# REF-IN-BLE-NS_4-0.net
KiCad netlist of a schematic drawn in EAGLE
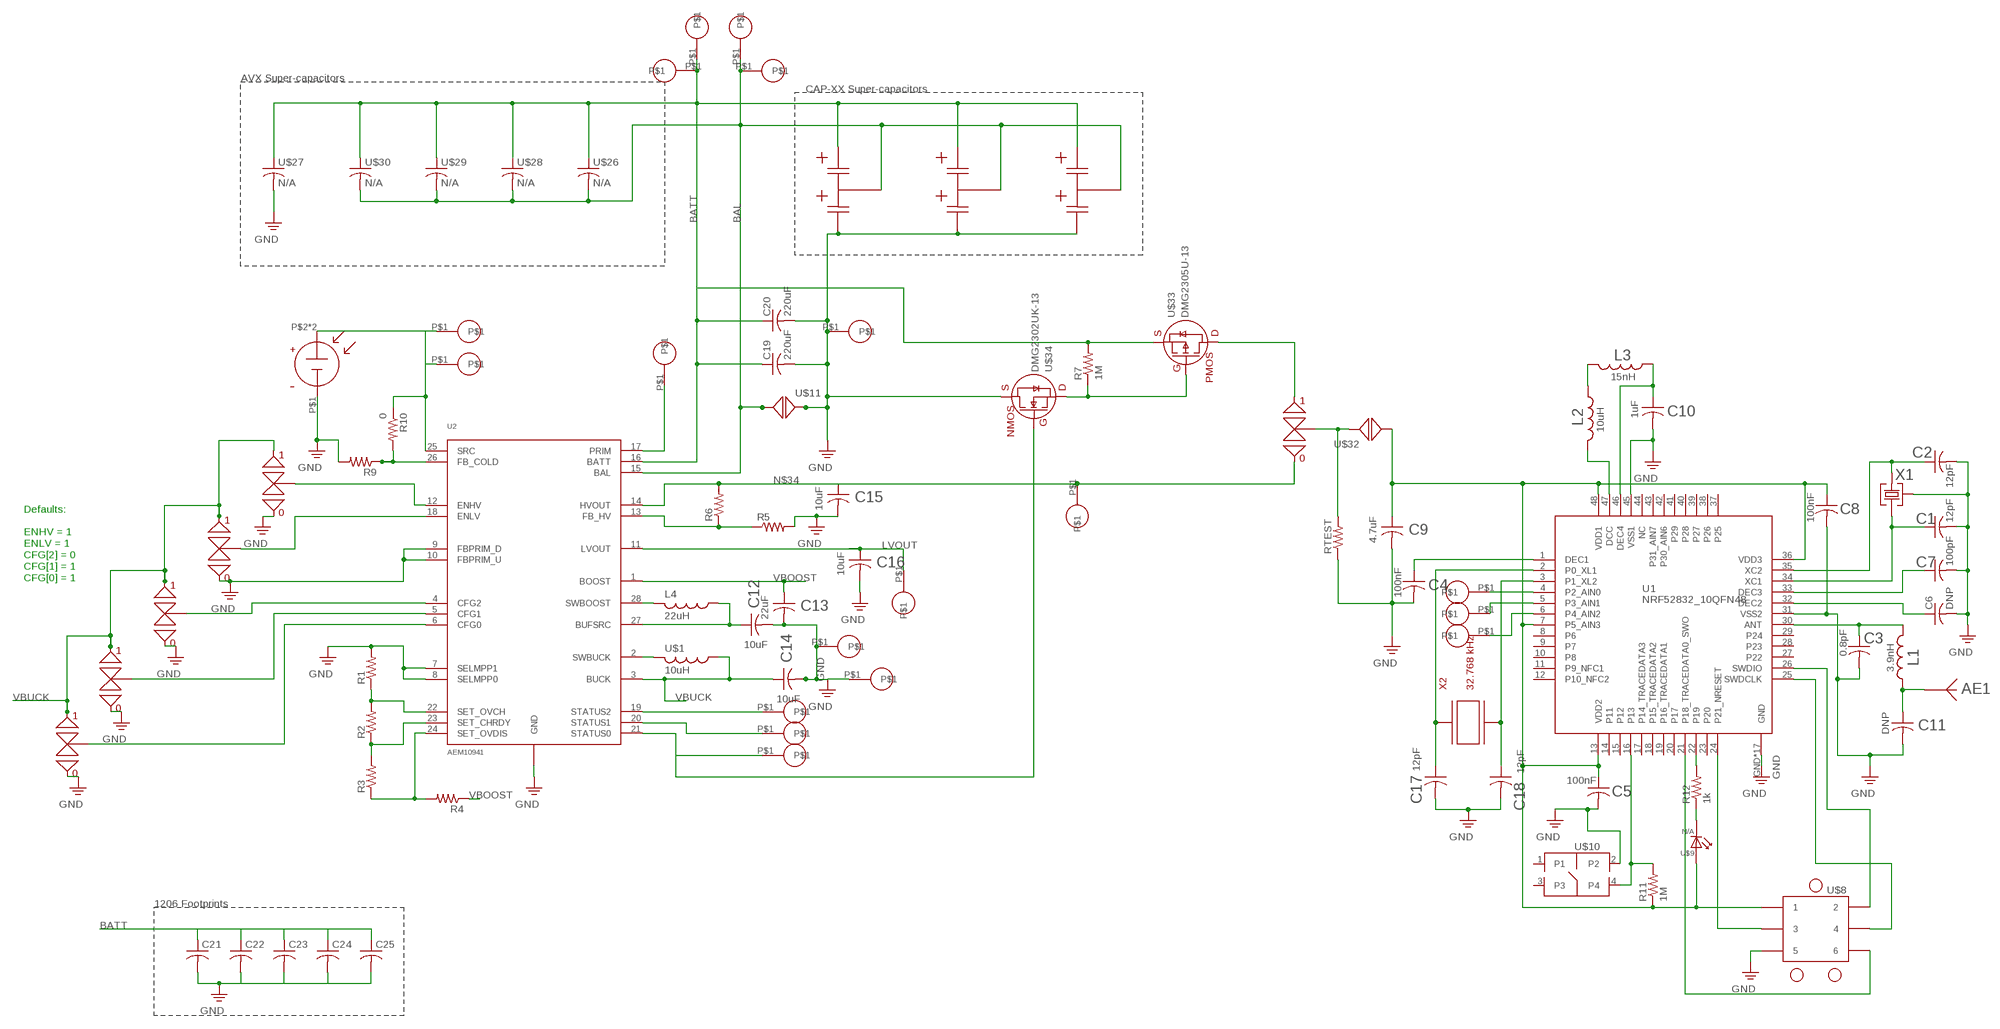
[diagram p0: schematic, sheet 1]

(export (version "E")
  (design (tool "Eeschema 10.0.6"))
  (components
    (comp (ref "AE1")
      (value "N/A")
      (footprint "eagle-import:BLE_ANTENNA_NORDIC")
      (libsource (lib "eagle-import") (part "2.4GHZ_ANTENNA"))
    )
    (comp (ref "C1")
      (value "12pF")
      (footprint "eagle-import:C0603")
      (fields (field (name "MFG_PART#") "C0603C120J5GACTU"))
      (libsource (lib "eagle-import") (part "C-USC0603T-12PF"))
    )
    (comp (ref "C2")
      (value "12pF")
      (footprint "eagle-import:C0603")
      (fields (field (name "MFG_PART#") "C0603C120J5GACTU"))
      (libsource (lib "eagle-import") (part "C-USC0603T-12PF"))
    )
    (comp (ref "C3")
      (value "0.8pF")
      (footprint "eagle-import:C0603")
      (fields (field (name "MFG_PART#") "CBR06C808B5GAC "))
      (libsource (lib "eagle-import") (part "C-USC0603T-0.8PF"))
    )
    (comp (ref "C4")
      (value "100nF")
      (footprint "eagle-import:C0603")
      (fields (field (name "MFG_PART#") "CL10B104KB8NNNC"))
      (libsource (lib "eagle-import") (part "C-USC0603T-100NF"))
    )
    (comp (ref "C5")
      (value "100nF")
      (footprint "eagle-import:C0603")
      (fields (field (name "MFG_PART#") "CL10B104KB8NNNC"))
      (libsource (lib "eagle-import") (part "C-USC0603T-100NF"))
    )
    (comp (ref "C6")
      (value "DNP")
      (footprint "eagle-import:C0603")
      (libsource (lib "eagle-import") (part "C-USC0603"))
    )
    (comp (ref "C7")
      (value "100pF")
      (footprint "eagle-import:C0603")
      (fields (field (name "MFG_PART#") "CL10C101JB8NNNC"))
      (libsource (lib "eagle-import") (part "C-USC0603T-100PF"))
    )
    (comp (ref "C8")
      (value "100nF")
      (footprint "eagle-import:C0603")
      (fields (field (name "MFG_PART#") "CL10B104KB8NNNC"))
      (libsource (lib "eagle-import") (part "C-USC0603T-100NF"))
    )
    (comp (ref "C9")
      (value "4.7uF")
      (footprint "eagle-import:C0603")
      (fields (field (name "MFG_PART#") "CL10A475KQ8NNWC "))
      (libsource (lib "eagle-import") (part "C-USC0603T-4.7UF"))
    )
    (comp (ref "C10")
      (value "1uF")
      (footprint "eagle-import:C0603")
      (fields (field (name "MFG_PART#") "CL10A105KP8NNNC ") (field (name "PERCENTAGE") "10%"))
      (libsource (lib "eagle-import") (part "C-USC0603T-1UF"))
    )
    (comp (ref "C11")
      (value "DNP")
      (footprint "eagle-import:C0603")
      (libsource (lib "eagle-import") (part "C-USC0603"))
    )
    (comp (ref "C12")
      (value "10uF")
      (footprint "eagle-import:C0603")
      (fields (field (name "MFG_PART#") "GRM188R61E106MA73D"))
      (libsource (lib "eagle-import") (part "C-USC0603T-10UF"))
    )
    (comp (ref "C13")
      (value "22uF")
      (footprint "eagle-import:C0603")
      (fields (field (name "MFG_PART#") "GRM188R61A226ME15D"))
      (libsource (lib "eagle-import") (part "C-USC0603T-22UF"))
    )
    (comp (ref "C14")
      (value "10uF")
      (footprint "eagle-import:C0603")
      (fields (field (name "MFG_PART#") "GRM188R61E106MA73D"))
      (libsource (lib "eagle-import") (part "C-USC0603T-10UF"))
    )
    (comp (ref "C15")
      (value "10uF")
      (footprint "eagle-import:C0603")
      (fields (field (name "MFG_PART#") "GRM188R61E106MA73D"))
      (libsource (lib "eagle-import") (part "C-USC0603T-10UF"))
    )
    (comp (ref "C16")
      (value "10uF")
      (footprint "eagle-import:C0603")
      (fields (field (name "MFG_PART#") "GRM188R61E106MA73D"))
      (libsource (lib "eagle-import") (part "C-USC0603T-10UF"))
    )
    (comp (ref "C17")
      (value "12pF")
      (footprint "eagle-import:C0603")
      (fields (field (name "MFG_PART#") "C0603C120J5GACTU"))
      (libsource (lib "eagle-import") (part "C-USC0603T-12PF"))
    )
    (comp (ref "C18")
      (value "12pF")
      (footprint "eagle-import:C0603")
      (fields (field (name "MFG_PART#") "C0603C120J5GACTU"))
      (libsource (lib "eagle-import") (part "C-USC0603T-12PF"))
    )
    (comp (ref "C19")
      (value "220uF")
      (footprint "eagle-import:C1206")
      (fields (field (name "MFG_PART#") "GRM31CC80G227ME11L"))
      (libsource (lib "eagle-import") (part "C-USC1206T-220UF"))
    )
    (comp (ref "C20")
      (value "220uF")
      (footprint "eagle-import:C1206")
      (fields (field (name "MFG_PART#") "GRM31CC80G227ME11L"))
      (libsource (lib "eagle-import") (part "C-USC1206T-220UF"))
    )
    (comp (ref "C21")
      (value "C-USC1206")
      (footprint "eagle-import:C1206")
      (libsource (lib "eagle-import") (part "C-USC1206"))
    )
    (comp (ref "C22")
      (value "C-USC1206")
      (footprint "eagle-import:C1206")
      (libsource (lib "eagle-import") (part "C-USC1206"))
    )
    (comp (ref "C23")
      (value "C-USC1206")
      (footprint "eagle-import:C1206")
      (libsource (lib "eagle-import") (part "C-USC1206"))
    )
    (comp (ref "C24")
      (value "C-USC1206")
      (footprint "eagle-import:C1206")
      (libsource (lib "eagle-import") (part "C-USC1206"))
    )
    (comp (ref "C25")
      (value "C-USC1206")
      (footprint "eagle-import:C1206")
      (libsource (lib "eagle-import") (part "C-USC1206"))
    )
    (comp (ref "L1")
      (value "3.9nH")
      (footprint "eagle-import:L0603")
      (fields (field (name "MFG_PART#") "L-14C3N9SV4T "))
      (libsource (lib "eagle-import") (part "L0603V-3.9NH"))
    )
    (comp (ref "L2")
      (value "10uH")
      (footprint "eagle-import:L0603")
      (fields (field (name "MFG_PART#") "LBR2012T100M"))
      (libsource (lib "eagle-import") (part "L0603V-10UH"))
    )
    (comp (ref "L3")
      (value "15nH")
      (footprint "eagle-import:L0603")
      (fields (field (name "MFG_PART#") "L-14C15NJV4T"))
      (libsource (lib "eagle-import") (part "L0603V-15NH"))
    )
    (comp (ref "L4")
      (value "22uH")
      (footprint "eagle-import:744031220")
      (fields (field (name "MFG_PART#") "744031220"))
      (libsource (lib "eagle-import") (part "744031220"))
    )
    (comp (ref "R1")
      (value "R-US_R0603")
      (footprint "eagle-import:R0603")
      (libsource (lib "eagle-import") (part "R-US_R0603"))
    )
    (comp (ref "R2")
      (value "R-US_R0603")
      (footprint "eagle-import:R0603")
      (libsource (lib "eagle-import") (part "R-US_R0603"))
    )
    (comp (ref "R3")
      (value "R-US_R0603")
      (footprint "eagle-import:R0603")
      (libsource (lib "eagle-import") (part "R-US_R0603"))
    )
    (comp (ref "R4")
      (value "R-US_R0603")
      (footprint "eagle-import:R0603")
      (libsource (lib "eagle-import") (part "R-US_R0603"))
    )
    (comp (ref "R5")
      (value "R-US_R0603")
      (footprint "eagle-import:R0603")
      (libsource (lib "eagle-import") (part "R-US_R0603"))
    )
    (comp (ref "R6")
      (value "R-US_R0603")
      (footprint "eagle-import:R0603")
      (libsource (lib "eagle-import") (part "R-US_R0603"))
    )
    (comp (ref "R7")
      (value "1M")
      (footprint "eagle-import:R0603")
      (libsource (lib "eagle-import") (part "R-US_R0603"))
    )
    (comp (ref "R9")
      (value "R-US_R0603")
      (footprint "eagle-import:R0603")
      (libsource (lib "eagle-import") (part "R-US_R0603"))
    )
    (comp (ref "R10")
      (value "0")
      (footprint "eagle-import:R0603")
      (libsource (lib "eagle-import") (part "R-US_R0603"))
    )
    (comp (ref "R11")
      (value "1M")
      (footprint "eagle-import:R0603")
      (libsource (lib "eagle-import") (part "R-US_R0603"))
    )
    (comp (ref "R12")
      (value "1k")
      (footprint "eagle-import:R0603")
      (libsource (lib "eagle-import") (part "R-US_R0603"))
    )
    (comp (ref "RTEST")
      (value "R-US_R0603")
      (footprint "eagle-import:R0603")
      (libsource (lib "eagle-import") (part "R-US_R0603"))
    )
    (comp (ref "U$1")
      (value "10uH")
      (footprint "eagle-import:L0603")
      (fields (field (name "MFG_PART#") "LBR2012T100M"))
      (libsource (lib "eagle-import") (part "L0603V-10UH"))
    )
    (comp (ref "U$2")
      (value "DOUBLE_SOLDER_BRIDGE1_CLOSED")
      (footprint "eagle-import:DOUBLE_SOLDER_BRIDGE_1_CLOSED")
      (libsource (lib "eagle-import") (part "DOUBLE_SOLDER_BRIDGE1_CLOSED"))
    )
    (comp (ref "U$3")
      (value "DOUBLE_SOLDER_BRIDGE1_CLOSED")
      (footprint "eagle-import:DOUBLE_SOLDER_BRIDGE_1_CLOSED")
      (libsource (lib "eagle-import") (part "DOUBLE_SOLDER_BRIDGE1_CLOSED"))
    )
    (comp (ref "U$4")
      (value "N/A")
      (footprint "eagle-import:DOUBLE_SOLDER_BRIDGE_0_CLOSED")
      (libsource (lib "eagle-import") (part "DOUBLE_SOLDER_BRIDGE0_CLOSED"))
    )
    (comp (ref "U$5")
      (value "DOUBLE_SOLDER_BRIDGE1_CLOSED")
      (footprint "eagle-import:DOUBLE_SOLDER_BRIDGE_1_CLOSED")
      (libsource (lib "eagle-import") (part "DOUBLE_SOLDER_BRIDGE1_CLOSED"))
    )
    (comp (ref "U$6")
      (value "DOUBLE_SOLDER_BRIDGE1_CLOSED")
      (footprint "eagle-import:DOUBLE_SOLDER_BRIDGE_1_CLOSED")
      (libsource (lib "eagle-import") (part "DOUBLE_SOLDER_BRIDGE1_CLOSED"))
    )
    (comp (ref "U$7")
      (value "N/A")
      (footprint "eagle-import:SOLAR_CELL_37X54MM")
      (libsource (lib "eagle-import") (part "SOLAR_CELL"))
    )
    (comp (ref "U$8")
      (value "N/A")
      (footprint "eagle-import:TC2030-IDC")
      (libsource (lib "eagle-import") (part "TC2030-IDC"))
    )
    (comp (ref "U$9")
      (value "N/A")
      (footprint "eagle-import:APT1608LZGCK")
      (fields (field (name "MFG_PART#") "APT1608LZGCK"))
      (libsource (lib "eagle-import") (part "APT1608LZGCK"))
    )
    (comp (ref "U$10")
      (value "MJTP1140")
      (footprint "eagle-import:MJTP1140A")
      (fields (field (name "MFG_PART#") "TL3315NF100Q "))
      (libsource (lib "eagle-import") (part "MJTP1140"))
    )
    (comp (ref "U$11")
      (value "SOLDER_BRIGDECLOSED")
      (footprint "eagle-import:SOLDER_BRIDGE_CLOSED")
      (libsource (lib "eagle-import") (part "SOLDER_BRIGDECLOSED"))
    )
    (comp (ref "U$12")
      (value "N/A")
      (footprint "eagle-import:1MM_PAD")
      (libsource (lib "eagle-import") (part "1MM_PAD"))
    )
    (comp (ref "U$13")
      (value "N/A")
      (footprint "eagle-import:1MM_PAD")
      (libsource (lib "eagle-import") (part "1MM_PAD"))
    )
    (comp (ref "U$14")
      (value "N/A")
      (footprint "eagle-import:1MM_PAD")
      (libsource (lib "eagle-import") (part "1MM_PAD"))
    )
    (comp (ref "U$15")
      (value "N/A")
      (footprint "eagle-import:1MM_PAD")
      (libsource (lib "eagle-import") (part "1MM_PAD"))
    )
    (comp (ref "U$16")
      (value "N/A")
      (footprint "eagle-import:1MM_PAD")
      (libsource (lib "eagle-import") (part "1MM_PAD"))
    )
    (comp (ref "U$17")
      (value "N/A")
      (footprint "eagle-import:1MM_PAD")
      (libsource (lib "eagle-import") (part "1MM_PAD"))
    )
    (comp (ref "U$18")
      (value "N/A")
      (footprint "eagle-import:1MM_PAD")
      (libsource (lib "eagle-import") (part "1MM_PAD"))
    )
    (comp (ref "U$19")
      (value "N/A")
      (footprint "eagle-import:1MM_PAD")
      (libsource (lib "eagle-import") (part "1MM_PAD"))
    )
    (comp (ref "U$20")
      (value "N/A")
      (footprint "eagle-import:1MM_PAD")
      (libsource (lib "eagle-import") (part "1MM_PAD"))
    )
    (comp (ref "U$21")
      (value "N/A")
      (footprint "eagle-import:1MM_PAD")
      (libsource (lib "eagle-import") (part "1MM_PAD"))
    )
    (comp (ref "U$22")
      (value "N/A")
      (footprint "eagle-import:1MM_PAD")
      (libsource (lib "eagle-import") (part "1MM_PAD"))
    )
    (comp (ref "U$23")
      (value "N/A")
      (footprint "eagle-import:CAP-XX_A-TYPE")
      (libsource (lib "eagle-import") (part "CAP-XX_A-TYPE"))
    )
    (comp (ref "U$24")
      (value "N/A")
      (footprint "eagle-import:CAP-XX_S-TYPE")
      (libsource (lib "eagle-import") (part "CAP-XX_S-TYPE"))
    )
    (comp (ref "U$25")
      (value "N/A")
      (footprint "eagle-import:CAP-XX_W-TYPE")
      (libsource (lib "eagle-import") (part "CAP-XX_W-TYPE"))
    )
    (comp (ref "U$26")
      (value "N/A")
      (footprint "eagle-import:BZ01_L-TYPE")
      (libsource (lib "eagle-import") (part "BZ01_L-TYPE"))
    )
    (comp (ref "U$27")
      (value "N/A")
      (footprint "eagle-import:BZ059_N-TYPE")
      (libsource (lib "eagle-import") (part "BZ059_N-TYPE"))
    )
    (comp (ref "U$28")
      (value "N/A")
      (footprint "eagle-import:BZ01_S-TYPE")
      (libsource (lib "eagle-import") (part "BZ01_S-TYPE"))
    )
    (comp (ref "U$29")
      (value "N/A")
      (footprint "eagle-import:BZ05_S-TYPE")
      (libsource (lib "eagle-import") (part "BZ05_S-TYPE"))
    )
    (comp (ref "U$30")
      (value "N/A")
      (footprint "eagle-import:BZ09_S-TYPE")
      (libsource (lib "eagle-import") (part "BZ09_S-TYPE"))
    )
    (comp (ref "U$31")
      (value "DOUBLE_SOLDER_BRIDGE1_CLOSED")
      (footprint "eagle-import:DOUBLE_SOLDER_BRIDGE_1_CLOSED")
      (libsource (lib "eagle-import") (part "DOUBLE_SOLDER_BRIDGE1_CLOSED"))
    )
    (comp (ref "U$32")
      (value "SOLDER_BRIGDECLOSED")
      (footprint "eagle-import:SOLDER_BRIDGE_CLOSED")
      (libsource (lib "eagle-import") (part "SOLDER_BRIGDECLOSED"))
    )
    (comp (ref "U$33")
      (value "DMG2305U-13")
      (footprint "eagle-import:SOT-23-3-DIODESINC")
      (libsource (lib "eagle-import") (part "DMG2305U-13"))
    )
    (comp (ref "U$34")
      (value "DMG2302UK-13")
      (footprint "eagle-import:SOT-23-3-DIODESINC")
      (libsource (lib "eagle-import") (part "DMG2302UK-13"))
    )
    (comp (ref "U$35")
      (value "N/A")
      (footprint "eagle-import:1MM_PAD")
      (libsource (lib "eagle-import") (part "1MM_PAD"))
    )
    (comp (ref "U$36")
      (value "N/A")
      (footprint "eagle-import:1MM_PAD")
      (libsource (lib "eagle-import") (part "1MM_PAD"))
    )
    (comp (ref "U$37")
      (value "N/A")
      (footprint "eagle-import:1MM_PAD")
      (libsource (lib "eagle-import") (part "1MM_PAD"))
    )
    (comp (ref "U$38")
      (value "N/A")
      (footprint "eagle-import:1MM_PAD")
      (libsource (lib "eagle-import") (part "1MM_PAD"))
    )
    (comp (ref "U$39")
      (value "N/A")
      (footprint "eagle-import:1MM_PAD")
      (libsource (lib "eagle-import") (part "1MM_PAD"))
    )
    (comp (ref "U$40")
      (value "N/A")
      (footprint "eagle-import:1MM_PAD")
      (libsource (lib "eagle-import") (part "1MM_PAD"))
    )
    (comp (ref "U$41")
      (value "N/A")
      (footprint "eagle-import:1MM_PAD")
      (libsource (lib "eagle-import") (part "1MM_PAD"))
    )
    (comp (ref "U1")
      (value "NRF52832_10QFN48")
      (footprint "eagle-import:NRF52832_10")
      (fields (field (name "MFG_PART#") "NRF52832-QFAA-R"))
      (libsource (lib "eagle-import") (part "NRF52832_10QFN48"))
    )
    (comp (ref "U2")
      (value "AEM10941")
      (footprint "eagle-import:QFN28_5X5_05PITCH")
      (fields (field (name "MFG_PART#") "AEM10941-QFN "))
      (libsource (lib "eagle-import") (part "AEM10941"))
    )
    (comp (ref "X1")
      (value "32 MHz")
      (footprint "eagle-import:FA-128-EPSON")
      (fields (field (name "MFG_PART#") "FA-128 32.0000MF10Z-AJ3"))
      (libsource (lib "eagle-import") (part "FA-128-32MHZMF10Z-AJ5"))
    )
    (comp (ref "X2")
      (value "32.768 kHz")
      (footprint "eagle-import:FC-135")
      (fields (field (name "MFG_PART#") "FC-135 32.7680KA-AC"))
      (libsource (lib "eagle-import") (part "FC-135_32.7680KA-AC"))
    )
  )
  (nets
    (net (code "1") (name "/BAL") (class "Default")
      (node (ref "U$11") (pin "P$1") (pinfunction "P1_P$1") (pintype "bidirectional"))
      (node (ref "U$19") (pin "P$1") (pinfunction "P$1_P$1") (pintype "bidirectional"))
      (node (ref "U$23") (pin "P$1") (pinfunction "BAL_P$1") (pintype "bidirectional"))
      (node (ref "U$24") (pin "P$1") (pinfunction "BAL_P$1") (pintype "bidirectional"))
      (node (ref "U$25") (pin "P$1") (pinfunction "BAL_P$1") (pintype "bidirectional"))
      (node (ref "U$26") (pin "P$3") (pinfunction "2_P$3") (pintype "passive"))
      (node (ref "U$26") (pin "P$4") (pinfunction "2_P$4") (pintype "passive"))
      (node (ref "U$28") (pin "P$3") (pinfunction "2_P$3") (pintype "passive"))
      (node (ref "U$29") (pin "P$3") (pinfunction "2_P$3") (pintype "passive"))
      (node (ref "U$30") (pin "P$3") (pinfunction "2_P$3") (pintype "passive"))
      (node (ref "U$41") (pin "P$1") (pinfunction "P$1_P$1") (pintype "bidirectional"))
      (node (ref "U2") (pin "15") (pinfunction "BAL_15") (pintype "bidirectional"))
    )
    (net (code "2") (name "/BATT") (class "Default")
      (node (ref "C19") (pin "1") (pinfunction "1_1") (pintype "passive"))
      (node (ref "C20") (pin "1") (pinfunction "1_1") (pintype "passive"))
      (node (ref "C21") (pin "1") (pinfunction "1_1") (pintype "passive"))
      (node (ref "C22") (pin "1") (pinfunction "1_1") (pintype "passive"))
      (node (ref "C23") (pin "1") (pinfunction "1_1") (pintype "passive"))
      (node (ref "C24") (pin "1") (pinfunction "1_1") (pintype "passive"))
      (node (ref "C25") (pin "1") (pinfunction "1_1") (pintype "passive"))
      (node (ref "R7") (pin "2") (pinfunction "2_2") (pintype "passive"))
      (node (ref "U$18") (pin "P$1") (pinfunction "P$1_P$1") (pintype "bidirectional"))
      (node (ref "U$23") (pin "P$2") (pinfunction "+_P$2") (pintype "bidirectional"))
      (node (ref "U$24") (pin "P$2") (pinfunction "+_P$2") (pintype "bidirectional"))
      (node (ref "U$25") (pin "P$2") (pinfunction "+_P$2") (pintype "bidirectional"))
      (node (ref "U$26") (pin "P$1") (pinfunction "1_P$1") (pintype "passive"))
      (node (ref "U$26") (pin "P$2") (pinfunction "1_P$2") (pintype "passive"))
      (node (ref "U$27") (pin "P$1") (pinfunction "1_P$1") (pintype "passive"))
      (node (ref "U$28") (pin "P$1") (pinfunction "1_P$1") (pintype "passive"))
      (node (ref "U$28") (pin "P$2") (pinfunction "1_P$2") (pintype "passive"))
      (node (ref "U$29") (pin "P$1") (pinfunction "1_P$1") (pintype "passive"))
      (node (ref "U$29") (pin "P$2") (pinfunction "1_P$2") (pintype "passive"))
      (node (ref "U$30") (pin "P$1") (pinfunction "1_P$1") (pintype "passive"))
      (node (ref "U$30") (pin "P$2") (pinfunction "1_P$2") (pintype "passive"))
      (node (ref "U$33") (pin "2") (pinfunction "S_2") (pintype "bidirectional"))
      (node (ref "U$40") (pin "P$1") (pinfunction "P$1_P$1") (pintype "bidirectional"))
      (node (ref "U2") (pin "16") (pinfunction "BATT_16") (pintype "bidirectional"))
    )
    (net (code "3") (name "/LVOUT") (class "Default")
      (node (ref "C16") (pin "1") (pinfunction "1_1") (pintype "passive"))
      (node (ref "U$16") (pin "P$1") (pinfunction "P$1_P$1") (pintype "bidirectional"))
      (node (ref "U2") (pin "11") (pinfunction "LVOUT_11") (pintype "output"))
    )
    (net (code "4") (name "/N$34") (class "Default")
      (node (ref "C15") (pin "1") (pinfunction "1_1") (pintype "passive"))
      (node (ref "R6") (pin "2") (pinfunction "2_2") (pintype "passive"))
      (node (ref "U$31") (pin "IN0") (pinfunction "IN0_IN0") (pintype "bidirectional"))
      (node (ref "U$37") (pin "P$1") (pinfunction "P$1_P$1") (pintype "bidirectional"))
      (node (ref "U2") (pin "14") (pinfunction "HVOUT_14") (pintype "output"))
    )
    (net (code "5") (name "/VBOOST") (class "Default")
      (node (ref "C13") (pin "1") (pinfunction "1_1") (pintype "passive"))
      (node (ref "R4") (pin "1") (pinfunction "1_1") (pintype "passive"))
      (node (ref "U2") (pin "1") (pinfunction "BOOST_1") (pintype "bidirectional"))
    )
    (net (code "6") (name "/VBUCK") (class "Default")
      (node (ref "C14") (pin "1") (pinfunction "1_1") (pintype "passive"))
      (node (ref "U$1") (pin "1") (pinfunction "1_1") (pintype "passive"))
      (node (ref "U$2") (pin "IN1") (pinfunction "IN1_IN1") (pintype "bidirectional"))
      (node (ref "U$3") (pin "IN1") (pinfunction "IN1_IN1") (pintype "bidirectional"))
      (node (ref "U$4") (pin "IN1") (pinfunction "IN1_IN1") (pintype "bidirectional"))
      (node (ref "U$5") (pin "IN1") (pinfunction "IN1_IN1") (pintype "bidirectional"))
      (node (ref "U$6") (pin "IN1") (pinfunction "IN1_IN1") (pintype "bidirectional"))
      (node (ref "U2") (pin "3") (pinfunction "BUCK_3") (pintype "bidirectional"))
    )
    (net (code "7") (name "GND") (class "Default")
      (node (ref "C1") (pin "2") (pinfunction "2_2") (pintype "passive"))
      (node (ref "C10") (pin "2") (pinfunction "2_2") (pintype "passive"))
      (node (ref "C11") (pin "2") (pinfunction "2_2") (pintype "passive"))
      (node (ref "C12") (pin "2") (pinfunction "2_2") (pintype "passive"))
      (node (ref "C13") (pin "2") (pinfunction "2_2") (pintype "passive"))
      (node (ref "C14") (pin "2") (pinfunction "2_2") (pintype "passive"))
      (node (ref "C15") (pin "2") (pinfunction "2_2") (pintype "passive"))
      (node (ref "C16") (pin "2") (pinfunction "2_2") (pintype "passive"))
      (node (ref "C17") (pin "2") (pinfunction "2_2") (pintype "passive"))
      (node (ref "C18") (pin "2") (pinfunction "2_2") (pintype "passive"))
      (node (ref "C19") (pin "2") (pinfunction "2_2") (pintype "passive"))
      (node (ref "C2") (pin "2") (pinfunction "2_2") (pintype "passive"))
      (node (ref "C20") (pin "2") (pinfunction "2_2") (pintype "passive"))
      (node (ref "C21") (pin "2") (pinfunction "2_2") (pintype "passive"))
      (node (ref "C22") (pin "2") (pinfunction "2_2") (pintype "passive"))
      (node (ref "C23") (pin "2") (pinfunction "2_2") (pintype "passive"))
      (node (ref "C24") (pin "2") (pinfunction "2_2") (pintype "passive"))
      (node (ref "C25") (pin "2") (pinfunction "2_2") (pintype "passive"))
      (node (ref "C3") (pin "2") (pinfunction "2_2") (pintype "passive"))
      (node (ref "C4") (pin "2") (pinfunction "2_2") (pintype "passive"))
      (node (ref "C5") (pin "2") (pinfunction "2_2") (pintype "passive"))
      (node (ref "C6") (pin "2") (pinfunction "2_2") (pintype "passive"))
      (node (ref "C7") (pin "2") (pinfunction "2_2") (pintype "passive"))
      (node (ref "C8") (pin "2") (pinfunction "2_2") (pintype "passive"))
      (node (ref "C9") (pin "2") (pinfunction "2_2") (pintype "passive"))
      (node (ref "R1") (pin "2") (pinfunction "2_2") (pintype "passive"))
      (node (ref "R5") (pin "2") (pinfunction "2_2") (pintype "passive"))
      (node (ref "R9") (pin "2") (pinfunction "2_2") (pintype "passive"))
      (node (ref "RTEST") (pin "1") (pinfunction "1_1") (pintype "passive"))
      (node (ref "U$10") (pin "2") (pinfunction "P2_2") (pintype "bidirectional"))
      (node (ref "U$11") (pin "P$2") (pinfunction "P2_P$2") (pintype "bidirectional"))
      (node (ref "U$17") (pin "P$1") (pinfunction "P$1_P$1") (pintype "bidirectional"))
      (node (ref "U$2") (pin "IN0") (pinfunction "IN0_IN0") (pintype "bidirectional"))
      (node (ref "U$23") (pin "P$3") (pinfunction "-_P$3") (pintype "bidirectional"))
      (node (ref "U$24") (pin "P$3") (pinfunction "-_P$3") (pintype "bidirectional"))
      (node (ref "U$25") (pin "P$3") (pinfunction "-_P$3") (pintype "bidirectional"))
      (node (ref "U$27") (pin "P$2") (pinfunction "2_P$2") (pintype "passive"))
      (node (ref "U$3") (pin "IN0") (pinfunction "IN0_IN0") (pintype "bidirectional"))
      (node (ref "U$34") (pin "3") (pinfunction "S_3") (pintype "bidirectional"))
      (node (ref "U$35") (pin "P$1") (pinfunction "P$1_P$1") (pintype "bidirectional"))
      (node (ref "U$38") (pin "P$1") (pinfunction "P$1_P$1") (pintype "bidirectional"))
      (node (ref "U$4") (pin "IN0") (pinfunction "IN0_IN0") (pintype "bidirectional"))
      (node (ref "U$5") (pin "IN0") (pinfunction "IN0_IN0") (pintype "bidirectional"))
      (node (ref "U$6") (pin "IN0") (pinfunction "IN0_IN0") (pintype "bidirectional"))
      (node (ref "U$7") (pin "P$1") (pinfunction "GND_P$1") (pintype "bidirectional"))
      (node (ref "U$8") (pin "P5") (pinfunction "5_P5") (pintype "bidirectional"))
      (node (ref "U1") (pin "31") (pinfunction "VSS2_31") (pintype "bidirectional"))
      (node (ref "U1") (pin "45") (pinfunction "VSS1_45") (pintype "bidirectional"))
      (node (ref "U1") (pin "GND") (pinfunction "GND_GND") (pintype "bidirectional"))
      (node (ref "U1") (pin "P$10") (pinfunction "GND_P$10") (pintype "bidirectional"))
      (node (ref "U1") (pin "P$11") (pinfunction "GND_P$11") (pintype "bidirectional"))
      (node (ref "U1") (pin "P$12") (pinfunction "GND_P$12") (pintype "bidirectional"))
      (node (ref "U1") (pin "P$13") (pinfunction "GND_P$13") (pintype "bidirectional"))
      (node (ref "U1") (pin "P$14") (pinfunction "GND_P$14") (pintype "bidirectional"))
      (node (ref "U1") (pin "P$15") (pinfunction "GND_P$15") (pintype "bidirectional"))
      (node (ref "U1") (pin "P$16") (pinfunction "GND_P$16") (pintype "bidirectional"))
      (node (ref "U1") (pin "P$17") (pinfunction "GND_P$17") (pintype "bidirectional"))
      (node (ref "U1") (pin "P$2") (pinfunction "GND_P$2") (pintype "bidirectional"))
      (node (ref "U1") (pin "P$3") (pinfunction "GND_P$3") (pintype "bidirectional"))
      (node (ref "U1") (pin "P$4") (pinfunction "GND_P$4") (pintype "bidirectional"))
      (node (ref "U1") (pin "P$5") (pinfunction "GND_P$5") (pintype "bidirectional"))
      (node (ref "U1") (pin "P$6") (pinfunction "GND_P$6") (pintype "bidirectional"))
      (node (ref "U1") (pin "P$7") (pinfunction "GND_P$7") (pintype "bidirectional"))
      (node (ref "U1") (pin "P$8") (pinfunction "GND_P$8") (pintype "bidirectional"))
      (node (ref "U1") (pin "P$9") (pinfunction "GND_P$9") (pintype "bidirectional"))
      (node (ref "U2") (pin "10") (pinfunction "FBPRIM_U_10") (pintype "bidirectional"))
      (node (ref "U2") (pin "7") (pinfunction "SELMPP1_7") (pintype "input"))
      (node (ref "U2") (pin "8") (pinfunction "SELMPP0_8") (pintype "input"))
      (node (ref "U2") (pin "9") (pinfunction "FBPRIM_D_9") (pintype "bidirectional"))
      (node (ref "U2") (pin "GND") (pinfunction "GND_GND") (pintype "power_in"))
      (node (ref "U2") (pin "GND1") (pinfunction "GND_GND1") (pintype "power_in"))
      (node (ref "U2") (pin "GND2") (pinfunction "GND_GND2") (pintype "power_in"))
      (node (ref "U2") (pin "GND3") (pinfunction "GND_GND3") (pintype "power_in"))
      (node (ref "U2") (pin "GND4") (pinfunction "GND_GND4") (pintype "power_in"))
      (node (ref "U2") (pin "GND5") (pinfunction "GND_GND5") (pintype "power_in"))
      (node (ref "X1") (pin "P2") (pinfunction "P3_P2") (pintype "bidirectional"))
      (node (ref "X1") (pin "P4") (pinfunction "P3_P4") (pintype "bidirectional"))
    )
    (net (code "8") (name "Net-(AE1-PadP$1)") (class "Default")
      (node (ref "AE1") (pin "P$1") (pinfunction "P$1_P$1") (pintype "bidirectional"))
      (node (ref "C11") (pin "1") (pinfunction "1_1") (pintype "passive"))
      (node (ref "L1") (pin "1") (pinfunction "1_1") (pintype "passive"))
    )
    (net (code "9") (name "Net-(L2-Pad1)") (class "Default")
      (node (ref "L2") (pin "1") (pinfunction "1_1") (pintype "passive"))
      (node (ref "L3") (pin "2") (pinfunction "2_2") (pintype "passive"))
    )
    (net (code "10") (name "Net-(L4-1)") (class "Default")
      (node (ref "C12") (pin "1") (pinfunction "1_1") (pintype "passive"))
      (node (ref "L4") (pin "PIN1") (pinfunction "1_PIN1") (pintype "passive"))
      (node (ref "U2") (pin "27") (pinfunction "BUFSRC_27") (pintype "bidirectional"))
    )
    (net (code "11") (name "Net-(L4-2)") (class "Default")
      (node (ref "L4") (pin "PIN2") (pinfunction "2_PIN2") (pintype "passive"))
      (node (ref "U2") (pin "28") (pinfunction "SWBOOST_28") (pintype "bidirectional"))
    )
    (net (code "12") (name "Net-(R12-Pad1)") (class "Default")
      (node (ref "R12") (pin "1") (pinfunction "1_1") (pintype "passive"))
      (node (ref "U$9") (pin "C") (pinfunction "C_C") (pintype "bidirectional"))
    )
    (net (code "13") (name "Net-(U$8-2)") (class "Default")
      (node (ref "U$8") (pin "P2") (pinfunction "2_P2") (pintype "bidirectional"))
      (node (ref "U1") (pin "26") (pinfunction "SWDIO_26") (pintype "bidirectional"))
    )
    (net (code "14") (name "Net-(U$8-3)") (class "Default")
      (node (ref "U$8") (pin "P3") (pinfunction "3_P3") (pintype "bidirectional"))
      (node (ref "U1") (pin "24") (pinfunction "P21_NRESET_24") (pintype "bidirectional"))
    )
    (net (code "15") (name "Net-(U$8-4)") (class "Default")
      (node (ref "U$8") (pin "P4") (pinfunction "4_P4") (pintype "bidirectional"))
      (node (ref "U1") (pin "25") (pinfunction "SWDCLK_25") (pintype "bidirectional"))
    )
    (net (code "16") (name "Net-(U$8-6)") (class "Default")
      (node (ref "U$8") (pin "P6") (pinfunction "6_P6") (pintype "bidirectional"))
      (node (ref "U1") (pin "21") (pinfunction "P18_TRACEDATA0_SWO_21") (pintype "bidirectional"))
    )
    (net (code "17") (name "Net-(U$10-P4)") (class "Default")
      (node (ref "R11") (pin "2") (pinfunction "2_2") (pintype "passive"))
      (node (ref "U$10") (pin "4") (pinfunction "P4_4") (pintype "bidirectional"))
      (node (ref "U1") (pin "16") (pinfunction "P13_16") (pintype "bidirectional"))
    )
    (net (code "18") (name "Net-(U$32-P1)") (class "Default")
      (node (ref "C5") (pin "1") (pinfunction "1_1") (pintype "passive"))
      (node (ref "C8") (pin "1") (pinfunction "1_1") (pintype "passive"))
      (node (ref "C9") (pin "1") (pinfunction "1_1") (pintype "passive"))
      (node (ref "R11") (pin "1") (pinfunction "1_1") (pintype "passive"))
      (node (ref "U$32") (pin "P$1") (pinfunction "P1_P$1") (pintype "bidirectional"))
      (node (ref "U$8") (pin "P1") (pinfunction "1_P1") (pintype "bidirectional"))
      (node (ref "U$9") (pin "A") (pinfunction "A_A") (pintype "bidirectional"))
      (node (ref "U1") (pin "13") (pinfunction "VDD2_13") (pintype "bidirectional"))
      (node (ref "U1") (pin "36") (pinfunction "VDD3_36") (pintype "bidirectional"))
      (node (ref "U1") (pin "48") (pinfunction "VDD1_48") (pintype "bidirectional"))
      (node (ref "U1") (pin "7") (pinfunction "P5_AIN3_7") (pintype "bidirectional"))
    )
    (net (code "19") (name "Net-(U$32-P2)") (class "Default")
      (node (ref "RTEST") (pin "2") (pinfunction "2_2") (pintype "passive"))
      (node (ref "U$31") (pin "OUT") (pinfunction "OUT_OUT") (pintype "bidirectional"))
      (node (ref "U$32") (pin "P$2") (pinfunction "P2_P$2") (pintype "bidirectional"))
    )
    (net (code "20") (name "Net-(U$33-D)") (class "Default")
      (node (ref "U$31") (pin "IN1") (pinfunction "IN1_IN1") (pintype "bidirectional"))
      (node (ref "U$33") (pin "3") (pinfunction "D_3") (pintype "bidirectional"))
    )
    (net (code "21") (name "Net-(U$33-G)") (class "Default")
      (node (ref "R7") (pin "1") (pinfunction "1_1") (pintype "passive"))
      (node (ref "U$33") (pin "1") (pinfunction "G_1") (pintype "bidirectional"))
      (node (ref "U$34") (pin "2") (pinfunction "D_2") (pintype "bidirectional"))
    )
    (net (code "22") (name "Net-(U$34-G)") (class "Default")
      (node (ref "U$15") (pin "P$1") (pinfunction "P$1_P$1") (pintype "bidirectional"))
      (node (ref "U$34") (pin "1") (pinfunction "G_1") (pintype "bidirectional"))
      (node (ref "U2") (pin "21") (pinfunction "STATUS0_21") (pintype "output"))
    )
    (net (code "23") (name "Net-(U1-ANT)") (class "Default")
      (node (ref "C3") (pin "1") (pinfunction "1_1") (pintype "passive"))
      (node (ref "L1") (pin "2") (pinfunction "2_2") (pintype "passive"))
      (node (ref "U1") (pin "30") (pinfunction "ANT_30") (pintype "bidirectional"))
    )
    (net (code "24") (name "Net-(U1-DCC)") (class "Default")
      (node (ref "L2") (pin "2") (pinfunction "2_2") (pintype "passive"))
      (node (ref "U1") (pin "47") (pinfunction "DCC_47") (pintype "bidirectional"))
    )
    (net (code "25") (name "Net-(U1-DEC1)") (class "Default")
      (node (ref "C4") (pin "1") (pinfunction "1_1") (pintype "passive"))
      (node (ref "U1") (pin "1") (pinfunction "DEC1_1") (pintype "bidirectional"))
    )
    (net (code "26") (name "Net-(U1-DEC2)") (class "Default")
      (node (ref "C6") (pin "1") (pinfunction "1_1") (pintype "passive"))
      (node (ref "U1") (pin "32") (pinfunction "DEC2_32") (pintype "bidirectional"))
    )
    (net (code "27") (name "Net-(U1-DEC3)") (class "Default")
      (node (ref "C7") (pin "1") (pinfunction "1_1") (pintype "passive"))
      (node (ref "U1") (pin "33") (pinfunction "DEC3_33") (pintype "bidirectional"))
    )
    (net (code "28") (name "Net-(U1-DEC4)") (class "Default")
      (node (ref "C10") (pin "1") (pinfunction "1_1") (pintype "passive"))
      (node (ref "L3") (pin "1") (pinfunction "1_1") (pintype "passive"))
      (node (ref "U1") (pin "46") (pinfunction "DEC4_46") (pintype "bidirectional"))
    )
    (net (code "29") (name "Net-(U1-P0_XL1)") (class "Default")
      (node (ref "C17") (pin "1") (pinfunction "1_1") (pintype "passive"))
      (node (ref "U1") (pin "2") (pinfunction "P0_XL1_2") (pintype "bidirectional"))
      (node (ref "X2") (pin "P$1") (pinfunction "P$1_P$1") (pintype "bidirectional"))
    )
    (net (code "30") (name "Net-(U1-P1_XL2)") (class "Default")
      (node (ref "C18") (pin "1") (pinfunction "1_1") (pintype "passive"))
      (node (ref "U1") (pin "3") (pinfunction "P1_XL2_3") (pintype "bidirectional"))
      (node (ref "X2") (pin "P$2") (pinfunction "P$2_P$2") (pintype "bidirectional"))
    )
    (net (code "31") (name "Net-(U1-P2_AIN0)") (class "Default")
      (node (ref "U$20") (pin "P$1") (pinfunction "P$1_P$1") (pintype "bidirectional"))
      (node (ref "U1") (pin "4") (pinfunction "P2_AIN0_4") (pintype "bidirectional"))
    )
    (net (code "32") (name "Net-(U1-P3_AIN1)") (class "Default")
      (node (ref "U$21") (pin "P$1") (pinfunction "P$1_P$1") (pintype "bidirectional"))
      (node (ref "U1") (pin "5") (pinfunction "P3_AIN1_5") (pintype "bidirectional"))
    )
    (net (code "33") (name "Net-(U1-P4_AIN2)") (class "Default")
      (node (ref "U$22") (pin "P$1") (pinfunction "P$1_P$1") (pintype "bidirectional"))
      (node (ref "U1") (pin "6") (pinfunction "P4_AIN2_6") (pintype "bidirectional"))
    )
    (net (code "34") (name "Net-(U1-P19)") (class "Default")
      (node (ref "R12") (pin "2") (pinfunction "2_2") (pintype "passive"))
      (node (ref "U1") (pin "22") (pinfunction "P19_22") (pintype "bidirectional"))
    )
    (net (code "35") (name "Net-(U1-XC1)") (class "Default")
      (node (ref "C1") (pin "1") (pinfunction "1_1") (pintype "passive"))
      (node (ref "U1") (pin "34") (pinfunction "XC1_34") (pintype "bidirectional"))
      (node (ref "X1") (pin "P3") (pinfunction "1_P3") (pintype "passive"))
    )
    (net (code "36") (name "Net-(U1-XC2)") (class "Default")
      (node (ref "C2") (pin "1") (pinfunction "1_1") (pintype "passive"))
      (node (ref "U1") (pin "35") (pinfunction "XC2_35") (pintype "bidirectional"))
      (node (ref "X1") (pin "P1") (pinfunction "2_P1") (pintype "passive"))
    )
    (net (code "37") (name "Net-(U2-CFG0)") (class "Default")
      (node (ref "U$6") (pin "OUT") (pinfunction "OUT_OUT") (pintype "bidirectional"))
      (node (ref "U2") (pin "6") (pinfunction "CFG0_6") (pintype "input"))
    )
    (net (code "38") (name "Net-(U2-CFG1)") (class "Default")
      (node (ref "U$5") (pin "OUT") (pinfunction "OUT_OUT") (pintype "bidirectional"))
      (node (ref "U2") (pin "5") (pinfunction "CFG1_5") (pintype "input"))
    )
    (net (code "39") (name "Net-(U2-CFG2)") (class "Default")
      (node (ref "U$4") (pin "OUT") (pinfunction "OUT_OUT") (pintype "bidirectional"))
      (node (ref "U2") (pin "4") (pinfunction "CFG2_4") (pintype "input"))
    )
    (net (code "40") (name "Net-(U2-ENHV)") (class "Default")
      (node (ref "U$2") (pin "OUT") (pinfunction "OUT_OUT") (pintype "bidirectional"))
      (node (ref "U2") (pin "12") (pinfunction "ENHV_12") (pintype "input"))
    )
    (net (code "41") (name "Net-(U2-ENLV)") (class "Default")
      (node (ref "U$3") (pin "OUT") (pinfunction "OUT_OUT") (pintype "bidirectional"))
      (node (ref "U2") (pin "18") (pinfunction "ENLV_18") (pintype "input"))
    )
    (net (code "42") (name "Net-(U2-FB_COLD)") (class "Default")
      (node (ref "R10") (pin "2") (pinfunction "2_2") (pintype "passive"))
      (node (ref "R9") (pin "1") (pinfunction "1_1") (pintype "passive"))
      (node (ref "U2") (pin "26") (pinfunction "FB_COLD_26") (pintype "bidirectional"))
    )
    (net (code "43") (name "Net-(U2-FB_HV)") (class "Default")
      (node (ref "R5") (pin "1") (pinfunction "1_1") (pintype "passive"))
      (node (ref "R6") (pin "1") (pinfunction "1_1") (pintype "passive"))
      (node (ref "U2") (pin "13") (pinfunction "FB_HV_13") (pintype "input"))
    )
    (net (code "44") (name "Net-(U2-PRIM)") (class "Default")
      (node (ref "U$12") (pin "P$1") (pinfunction "P$1_P$1") (pintype "bidirectional"))
      (node (ref "U2") (pin "17") (pinfunction "PRIM_17") (pintype "bidirectional"))
    )
    (net (code "45") (name "Net-(U2-SET_CHRDY)") (class "Default")
      (node (ref "R2") (pin "1") (pinfunction "1_1") (pintype "passive"))
      (node (ref "R3") (pin "2") (pinfunction "2_2") (pintype "passive"))
      (node (ref "U2") (pin "23") (pinfunction "SET_CHRDY_23") (pintype "bidirectional"))
    )
    (net (code "46") (name "Net-(U2-SET_OVCH)") (class "Default")
      (node (ref "R1") (pin "1") (pinfunction "1_1") (pintype "passive"))
      (node (ref "R2") (pin "2") (pinfunction "2_2") (pintype "passive"))
      (node (ref "U2") (pin "22") (pinfunction "SET_OVCH_22") (pintype "bidirectional"))
    )
    (net (code "47") (name "Net-(U2-SET_OVDIS)") (class "Default")
      (node (ref "R3") (pin "1") (pinfunction "1_1") (pintype "passive"))
      (node (ref "R4") (pin "2") (pinfunction "2_2") (pintype "passive"))
      (node (ref "U2") (pin "24") (pinfunction "SET_OVDIS_24") (pintype "bidirectional"))
    )
    (net (code "48") (name "Net-(U2-SRC)") (class "Default")
      (node (ref "R10") (pin "1") (pinfunction "1_1") (pintype "passive"))
      (node (ref "U$36") (pin "P$1") (pinfunction "P$1_P$1") (pintype "bidirectional"))
      (node (ref "U$39") (pin "P$1") (pinfunction "P$1_P$1") (pintype "bidirectional"))
      (node (ref "U$7") (pin "P$2") (pinfunction "VOUT_P$2") (pintype "bidirectional"))
      (node (ref "U$7") (pin "P$3") (pinfunction "VOUT_P$3") (pintype "bidirectional"))
      (node (ref "U2") (pin "25") (pinfunction "SRC_25") (pintype "input"))
    )
    (net (code "49") (name "Net-(U2-STATUS1)") (class "Default")
      (node (ref "U$14") (pin "P$1") (pinfunction "P$1_P$1") (pintype "bidirectional"))
      (node (ref "U2") (pin "20") (pinfunction "STATUS1_20") (pintype "output"))
    )
    (net (code "50") (name "Net-(U2-STATUS2)") (class "Default")
      (node (ref "U$13") (pin "P$1") (pinfunction "P$1_P$1") (pintype "bidirectional"))
      (node (ref "U2") (pin "19") (pinfunction "STATUS2_19") (pintype "output"))
    )
    (net (code "51") (name "Net-(U2-SWBUCK)") (class "Default")
      (node (ref "U$1") (pin "2") (pinfunction "2_2") (pintype "passive"))
      (node (ref "U2") (pin "2") (pinfunction "SWBUCK_2") (pintype "bidirectional"))
    )
    (net (code "52") (name "unconnected-(U$10-P1-Pad1)") (class "Default")
      (node (ref "U$10") (pin "1") (pinfunction "P1_1") (pintype "bidirectional"))
    )
    (net (code "53") (name "unconnected-(U$10-P3-Pad3)") (class "Default")
      (node (ref "U$10") (pin "3") (pinfunction "P3_3") (pintype "bidirectional"))
    )
    (net (code "54") (name "unconnected-(U1-NC-Pad44)") (class "Default")
      (node (ref "U1") (pin "44") (pinfunction "NC_44") (pintype "bidirectional"))
    )
    (net (code "55") (name "unconnected-(U1-P6-Pad8)") (class "Default")
      (node (ref "U1") (pin "8") (pinfunction "P6_8") (pintype "bidirectional"))
    )
    (net (code "56") (name "unconnected-(U1-P7-Pad9)") (class "Default")
      (node (ref "U1") (pin "9") (pinfunction "P7_9") (pintype "bidirectional"))
    )
    (net (code "57") (name "unconnected-(U1-P8-Pad10)") (class "Default")
      (node (ref "U1") (pin "10") (pinfunction "P8_10") (pintype "bidirectional"))
    )
    (net (code "58") (name "unconnected-(U1-P9_NFC1-Pad11)") (class "Default")
      (node (ref "U1") (pin "11") (pinfunction "P9_NFC1_11") (pintype "bidirectional"))
    )
    (net (code "59") (name "unconnected-(U1-P10_NFC2-Pad12)") (class "Default")
      (node (ref "U1") (pin "12") (pinfunction "P10_NFC2_12") (pintype "bidirectional"))
    )
    (net (code "60") (name "unconnected-(U1-P11-Pad14)") (class "Default")
      (node (ref "U1") (pin "14") (pinfunction "P11_14") (pintype "bidirectional"))
    )
    (net (code "61") (name "unconnected-(U1-P12-Pad15)") (class "Default")
      (node (ref "U1") (pin "15") (pinfunction "P12_15") (pintype "bidirectional"))
    )
    (net (code "62") (name "unconnected-(U1-P14_TRACEDATA3-Pad17)") (class "Default")
      (node (ref "U1") (pin "17") (pinfunction "P14_TRACEDATA3_17") (pintype "bidirectional"))
    )
    (net (code "63") (name "unconnected-(U1-P15_TRACEDATA2-Pad18)") (class "Default")
      (node (ref "U1") (pin "18") (pinfunction "P15_TRACEDATA2_18") (pintype "bidirectional"))
    )
    (net (code "64") (name "unconnected-(U1-P16_TRACEDATA1-Pad19)") (class "Default")
      (node (ref "U1") (pin "19") (pinfunction "P16_TRACEDATA1_19") (pintype "bidirectional"))
    )
    (net (code "65") (name "unconnected-(U1-P17-Pad20)") (class "Default")
      (node (ref "U1") (pin "20") (pinfunction "P17_20") (pintype "bidirectional"))
    )
    (net (code "66") (name "unconnected-(U1-P20-Pad23)") (class "Default")
      (node (ref "U1") (pin "23") (pinfunction "P20_23") (pintype "bidirectional"))
    )
    (net (code "67") (name "unconnected-(U1-P22-Pad27)") (class "Default")
      (node (ref "U1") (pin "27") (pinfunction "P22_27") (pintype "bidirectional"))
    )
    (net (code "68") (name "unconnected-(U1-P23-Pad28)") (class "Default")
      (node (ref "U1") (pin "28") (pinfunction "P23_28") (pintype "bidirectional"))
    )
    (net (code "69") (name "unconnected-(U1-P24-Pad29)") (class "Default")
      (node (ref "U1") (pin "29") (pinfunction "P24_29") (pintype "bidirectional"))
    )
    (net (code "70") (name "unconnected-(U1-P25-Pad37)") (class "Default")
      (node (ref "U1") (pin "37") (pinfunction "P25_37") (pintype "bidirectional"))
    )
    (net (code "71") (name "unconnected-(U1-P26-Pad38)") (class "Default")
      (node (ref "U1") (pin "38") (pinfunction "P26_38") (pintype "bidirectional"))
    )
    (net (code "72") (name "unconnected-(U1-P27-Pad39)") (class "Default")
      (node (ref "U1") (pin "39") (pinfunction "P27_39") (pintype "bidirectional"))
    )
    (net (code "73") (name "unconnected-(U1-P28-Pad40)") (class "Default")
      (node (ref "U1") (pin "40") (pinfunction "P28_40") (pintype "bidirectional"))
    )
    (net (code "74") (name "unconnected-(U1-P29-Pad41)") (class "Default")
      (node (ref "U1") (pin "41") (pinfunction "P29_41") (pintype "bidirectional"))
    )
    (net (code "75") (name "unconnected-(U1-P30_AIN6-Pad42)") (class "Default")
      (node (ref "U1") (pin "42") (pinfunction "P30_AIN6_42") (pintype "bidirectional"))
    )
    (net (code "76") (name "unconnected-(U1-P31_AIN7-Pad43)") (class "Default")
      (node (ref "U1") (pin "43") (pinfunction "P31_AIN7_43") (pintype "bidirectional"))
    )
  )
)
